# PumpTimerV2.net
KiCad netlist of a schematic drawn in Altium Designer
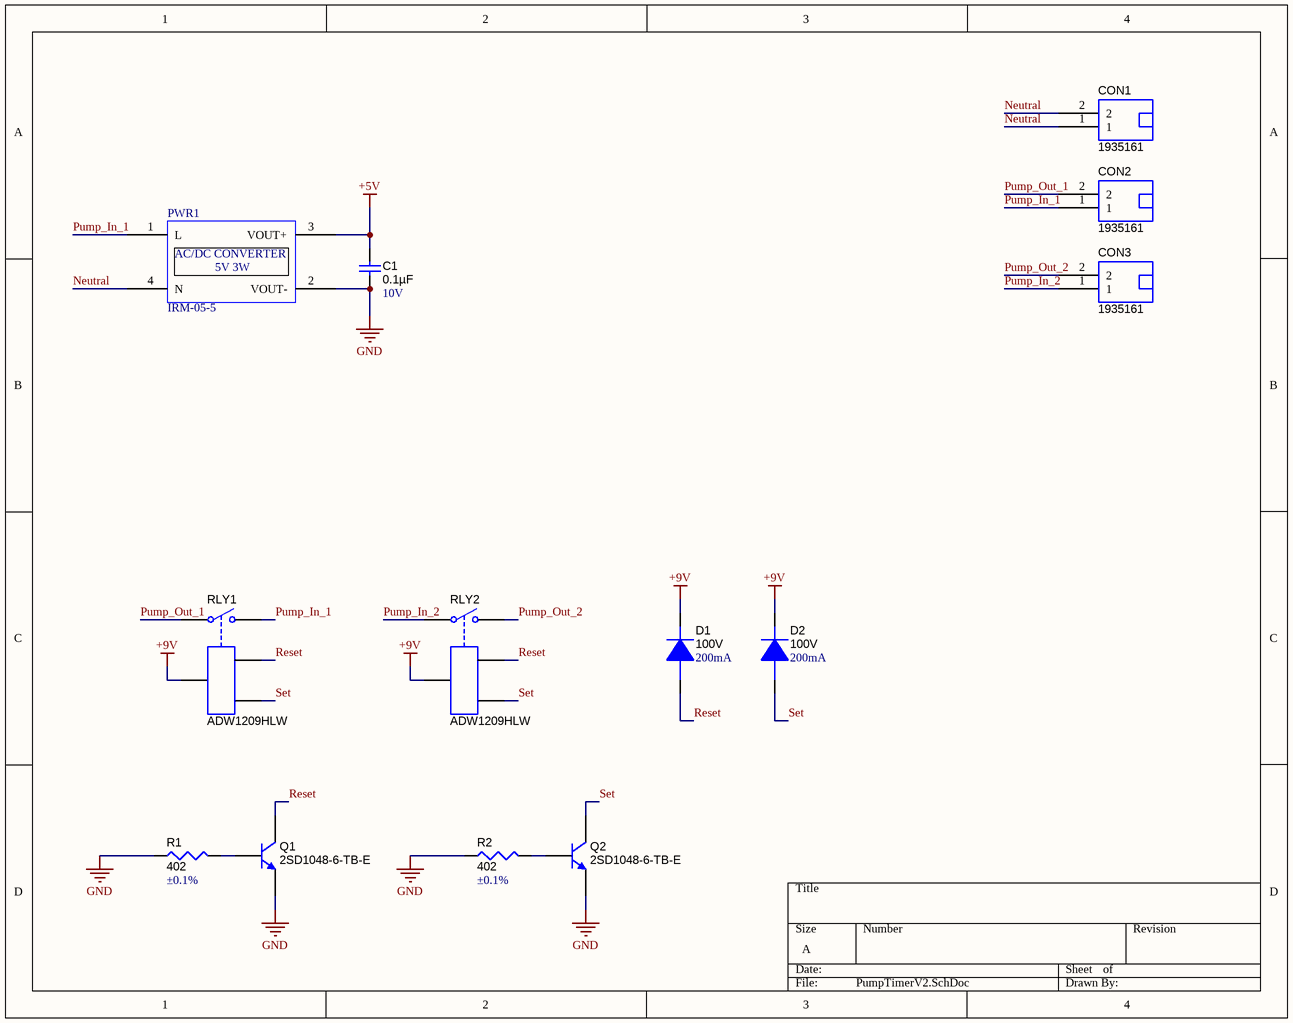
[diagram p0: PumpTimerV2.SchDoc]

(export (version "E")
  (design (tool "Eeschema 10.0.6"))
  (components
    (comp (ref "C1")
      (value "0.1µF")
      (footprint "0402_C")
      (description "CAP CER 0.1UF 10V 10% X7R 0402")
      (fields
        (field (name "MANUFACTURER PART NUMBER") "C1005X7R1A104K050BB")
        (field (name "MANUFACTURER") "TDK Corporation")
        (field (name "PARAMETERS") "10V")
      )
      (libsource (lib "Lynntech Instrumentation") (part "Capacitor{colon} Ceramic"))
    )
    (comp (ref "CON1")
      (value "1935161")
      (footprint "5MM-CON-2")
      (fields (field (name "MANUFACTURER") "Phoenix Contact"))
      (libsource (lib "Lynntech Instrumentation") (part "JST{colon} B2B-PH-K-S(LF)(SN)"))
    )
    (comp (ref "CON2")
      (value "1935161")
      (footprint "5MM-CON-2")
      (fields (field (name "MANUFACTURER") "Phoenix Contact"))
      (libsource (lib "Lynntech Instrumentation") (part "JST{colon} B2B-PH-K-S(LF)(SN)"))
    )
    (comp (ref "CON3")
      (value "1935161")
      (footprint "5MM-CON-2")
      (fields (field (name "MANUFACTURER") "Phoenix Contact"))
      (libsource (lib "Lynntech Instrumentation") (part "JST{colon} B2B-PH-K-S(LF)(SN)"))
    )
    (comp (ref "D1")
      (value "100V")
      (footprint "SOD123")
      (description "DIODE GEN PURP 100V 200MA SOD123")
      (fields
        (field (name "MANUFACTURER PART NUMBER") "MMSD914T1G")
        (field (name "MANUFACTURER") "ON Semiconductor")
        (field (name "PARAMETERS") "200mA")
      )
      (libsource (lib "Lynntech Instrumentation") (part "DIODE"))
    )
    (comp (ref "D2")
      (value "100V")
      (footprint "SOD123")
      (description "DIODE GEN PURP 100V 200MA SOD123")
      (fields
        (field (name "MANUFACTURER PART NUMBER") "MMSD914T1G")
        (field (name "MANUFACTURER") "ON Semiconductor")
        (field (name "PARAMETERS") "200mA")
      )
      (libsource (lib "Lynntech Instrumentation") (part "DIODE"))
    )
    (comp (ref "PWR1")
      (value "IRM-05-5")
      (footprint "RAC03-05SK")
      (description "AC/DC CONVERTER 5V 3W")
      (fields
        (field (name "MANUFACTURER PART NUMBER") "RAC03-05SK")
        (field (name "MANUFACTURER") "Recom Power")
      )
      (libsource (lib "Lynntech Instrumentation") (part "RAC03-05SK"))
    )
    (comp (ref "Q1")
      (value "2SD1048-6-TB-E")
      (footprint "SOT-23")
      (description "BIPOLAR (BJT) TRANSISTOR NPN 15V 700MA 250MHZ 200MW SURFACE MOUNT 3-CP")
      (fields (field (name "MANUFACTURER") "ON Semiconductor"))
      (libsource (lib "Lynntech Instrumentation") (part "2N3904"))
    )
    (comp (ref "Q2")
      (value "2SD1048-6-TB-E")
      (footprint "SOT-23")
      (description "BIPOLAR (BJT) TRANSISTOR NPN 15V 700MA 250MHZ 200MW SURFACE MOUNT 3-CP")
      (fields (field (name "MANUFACTURER") "ON Semiconductor"))
      (libsource (lib "Lynntech Instrumentation") (part "2N3904"))
    )
    (comp (ref "R1")
      (value "402")
      (footprint "0805_R")
      (description "RES 402 OHM 1/10W .1% 0805 SMD")
      (fields
        (field (name "MANUFACTURER PART NUMBER") "RR1220P-4020-B-M-T5")
        (field (name "MANUFACTURER") "Susumu")
        (field (name "PARAMETERS") "±0.1%")
      )
      (libsource (lib "Lynntech Instrumentation") (part "Resistor"))
    )
    (comp (ref "R2")
      (value "402")
      (footprint "0805_R")
      (description "RES 402 OHM 1/10W .1% 0805 SMD")
      (fields
        (field (name "MANUFACTURER PART NUMBER") "RR1220P-4020-B-M-T5")
        (field (name "MANUFACTURER") "Susumu")
        (field (name "PARAMETERS") "±0.1%")
      )
      (libsource (lib "Lynntech Instrumentation") (part "Resistor"))
    )
    (comp (ref "RLY1")
      (value "ADW1209HLW")
      (footprint "ADW1 LOW-PROFILE RELAY")
      (description "GENERAL PURPOSE TWO-COIL RELAY SPST-NO (1 FORM A) 9VDC COIL THROUGH HOLE")
      (fields (field (name "MANUFACTURER") "Panasonic - ECG"))
      (libsource (lib "Lynntech Instrumentation") (part "RELAY{colon} SPST_TWO-COIL"))
    )
    (comp (ref "RLY2")
      (value "ADW1209HLW")
      (footprint "ADW1 LOW-PROFILE RELAY")
      (description "GENERAL PURPOSE TWO-COIL RELAY SPST-NO (1 FORM A) 9VDC COIL THROUGH HOLE")
      (fields (field (name "MANUFACTURER") "Panasonic - ECG"))
      (libsource (lib "Lynntech Instrumentation") (part "RELAY{colon} SPST_TWO-COIL"))
    )
  )
  (nets
    (net (code "1") (name "+5V") (class "Default")
      (node (ref "C1") (pin "2") (pinfunction "2_2") (pintype "passive"))
      (node (ref "PWR1") (pin "3") (pinfunction "VOUT+_3") (pintype "passive"))
    )
    (net (code "2") (name "+9V") (class "Default")
      (node (ref "D1") (pin "2") (pinfunction "K_2") (pintype "passive"))
      (node (ref "D2") (pin "2") (pinfunction "K_2") (pintype "passive"))
      (node (ref "RLY1") (pin "2") (pinfunction "2_2") (pintype "passive"))
      (node (ref "RLY2") (pin "2") (pinfunction "2_2") (pintype "passive"))
    )
    (net (code "3") (name "/Neutral") (class "Default")
      (node (ref "CON1") (pin "1") (pinfunction "1_1") (pintype "passive"))
      (node (ref "CON1") (pin "2") (pinfunction "2_2") (pintype "passive"))
      (node (ref "PWR1") (pin "4") (pinfunction "N_4") (pintype "passive"))
    )
    (net (code "4") (name "/Pump_In_1") (class "Default")
      (node (ref "CON2") (pin "1") (pinfunction "1_1") (pintype "passive"))
      (node (ref "PWR1") (pin "1") (pinfunction "L_1") (pintype "passive"))
      (node (ref "RLY1") (pin "4") (pinfunction "4_4") (pintype "passive"))
    )
    (net (code "5") (name "/Pump_In_2") (class "Default")
      (node (ref "CON3") (pin "1") (pinfunction "1_1") (pintype "passive"))
      (node (ref "RLY2") (pin "5") (pinfunction "5_5") (pintype "passive"))
    )
    (net (code "6") (name "/Pump_Out_1") (class "Default")
      (node (ref "CON2") (pin "2") (pinfunction "2_2") (pintype "passive"))
      (node (ref "RLY1") (pin "5") (pinfunction "5_5") (pintype "passive"))
    )
    (net (code "7") (name "/Pump_Out_2") (class "Default")
      (node (ref "CON3") (pin "2") (pinfunction "2_2") (pintype "passive"))
      (node (ref "RLY2") (pin "4") (pinfunction "4_4") (pintype "passive"))
    )
    (net (code "8") (name "/Reset") (class "Default")
      (node (ref "D1") (pin "1") (pinfunction "A_1") (pintype "passive"))
      (node (ref "Q1") (pin "C") (pinfunction "C_C") (pintype "passive"))
      (node (ref "RLY1") (pin "3") (pinfunction "3_3") (pintype "passive"))
      (node (ref "RLY2") (pin "3") (pinfunction "3_3") (pintype "passive"))
    )
    (net (code "9") (name "/Set") (class "Default")
      (node (ref "D2") (pin "1") (pinfunction "A_1") (pintype "passive"))
      (node (ref "Q2") (pin "C") (pinfunction "C_C") (pintype "passive"))
      (node (ref "RLY1") (pin "1") (pinfunction "1_1") (pintype "passive"))
      (node (ref "RLY2") (pin "1") (pinfunction "1_1") (pintype "passive"))
    )
    (net (code "10") (name "GND") (class "Default")
      (node (ref "C1") (pin "1") (pinfunction "1_1") (pintype "passive"))
      (node (ref "PWR1") (pin "2") (pinfunction "VOUT-_2") (pintype "passive"))
      (node (ref "Q1") (pin "E") (pinfunction "E_E") (pintype "passive"))
      (node (ref "Q2") (pin "E") (pinfunction "E_E") (pintype "passive"))
      (node (ref "R1") (pin "1") (pinfunction "1_1") (pintype "passive"))
      (node (ref "R2") (pin "1") (pinfunction "1_1") (pintype "passive"))
    )
    (net (code "11") (name "Net-(Q1-PadB)") (class "Default")
      (node (ref "Q1") (pin "B") (pinfunction "B_B") (pintype "passive"))
      (node (ref "R1") (pin "2") (pinfunction "2_2") (pintype "passive"))
    )
    (net (code "12") (name "Net-(Q2-PadB)") (class "Default")
      (node (ref "Q2") (pin "B") (pinfunction "B_B") (pintype "passive"))
      (node (ref "R2") (pin "2") (pinfunction "2_2") (pintype "passive"))
    )
  )
)
